# FPGA-DemoShield-Schematic.net
KiCad netlist of a schematic drawn in Altium Designer
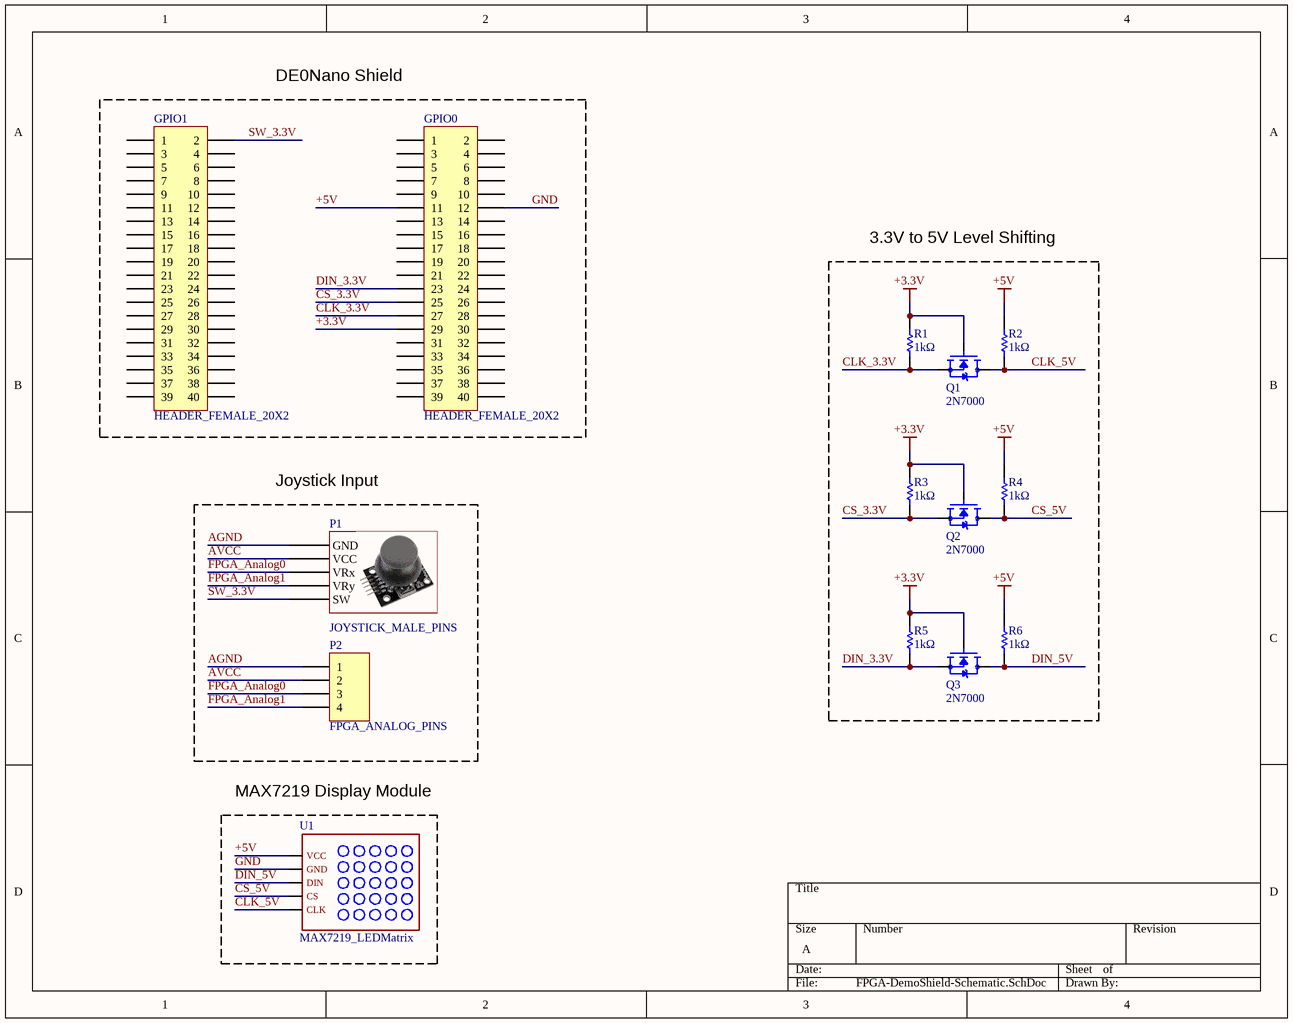
[diagram p0: FPGA-DemoShield-Schematic.SchDoc]

(export (version "E")
  (design (tool "Eeschema 10.0.6"))
  (components
    (comp (ref "GPIO0")
      (value "HEADER_FEMALE_20X2")
      (footprint "HDR2X20_FEMALE")
      (description "Header, 20-Pin, Dual row")
      (libsource (lib "FPGA-DemoShield-SchLib") (part "HEADER_FEMALE_20X2"))
    )
    (comp (ref "GPIO1")
      (value "HEADER_FEMALE_20X2")
      (footprint "HDR2X20_FEMALE")
      (description "Header, 20-Pin, Dual row")
      (libsource (lib "FPGA-DemoShield-SchLib") (part "HEADER_FEMALE_20X2"))
    )
    (comp (ref "P1")
      (value "JOYSTICK_MALE_PINS")
      (footprint "HDR1X5_MALE")
      (description "Header, 5-Pin")
      (libsource (lib "FPGA-DemoShield-SchLib") (part "JOYSTICK_MALE_PINS"))
    )
    (comp (ref "P2")
      (value "FPGA_ANALOG_PINS")
      (footprint "HDR1X4_MALE")
      (description "Header, 4-Pin")
      (libsource (lib "FPGA-DemoShield-SchLib") (part "FPGA_ANALOG_PINS"))
    )
    (comp (ref "Q1")
      (value "2N7000")
      (footprint "2N7000-TO-92")
      (description "MOSFET N-CH 60V 350MA TO92-3")
      (libsource (lib "FPGA-DemoShield-SchLib") (part "2N7000"))
    )
    (comp (ref "Q2")
      (value "2N7000")
      (footprint "2N7000-TO-92")
      (description "MOSFET N-CH 60V 350MA TO92-3")
      (libsource (lib "FPGA-DemoShield-SchLib") (part "2N7000"))
    )
    (comp (ref "Q3")
      (value "2N7000")
      (footprint "2N7000-TO-92")
      (description "MOSFET N-CH 60V 350MA TO92-3")
      (libsource (lib "FPGA-DemoShield-SchLib") (part "2N7000"))
    )
    (comp (ref "R1")
      (value "1kΩ")
      (footprint "RES_0805")
      (description "1k RES 0805")
      (fields (field (name "Comment") "RES_1k_0805") (field (name "PUBLISHER") "Altium Limited"))
      (libsource (lib "FPGA-DemoShield-SchLib") (part "RES_1k_0805"))
    )
    (comp (ref "R2")
      (value "1kΩ")
      (footprint "RES_0805")
      (description "1k RES 0805")
      (fields (field (name "Comment") "RES_1k_0805") (field (name "PUBLISHER") "Altium Limited"))
      (libsource (lib "FPGA-DemoShield-SchLib") (part "RES_1k_0805"))
    )
    (comp (ref "R3")
      (value "1kΩ")
      (footprint "RES_0805")
      (description "1k RES 0805")
      (fields (field (name "Comment") "RES_1k_0805") (field (name "PUBLISHER") "Altium Limited"))
      (libsource (lib "FPGA-DemoShield-SchLib") (part "RES_1k_0805"))
    )
    (comp (ref "R4")
      (value "1kΩ")
      (footprint "RES_0805")
      (description "1k RES 0805")
      (fields (field (name "Comment") "RES_1k_0805") (field (name "PUBLISHER") "Altium Limited"))
      (libsource (lib "FPGA-DemoShield-SchLib") (part "RES_1k_0805"))
    )
    (comp (ref "R5")
      (value "1kΩ")
      (footprint "RES_0805")
      (description "1k RES 0805")
      (fields (field (name "Comment") "RES_1k_0805") (field (name "PUBLISHER") "Altium Limited"))
      (libsource (lib "FPGA-DemoShield-SchLib") (part "RES_1k_0805"))
    )
    (comp (ref "R6")
      (value "1kΩ")
      (footprint "RES_0805")
      (description "1k RES 0805")
      (fields (field (name "Comment") "RES_1k_0805") (field (name "PUBLISHER") "Altium Limited"))
      (libsource (lib "FPGA-DemoShield-SchLib") (part "RES_1k_0805"))
    )
    (comp (ref "U1")
      (value "MAX7219_LEDMatrix")
      (footprint "LED_MATRIX")
      (description "LED MATRIX")
      (libsource (lib "FPGA-DemoShield-SchLib") (part "MAX7219_LEDMatrix"))
    )
  )
  (nets
    (net (code "1") (name "+3.3V") (class "Default")
      (node (ref "GPIO0") (pin "29") (pinfunction "29_29") (pintype "passive"))
      (node (ref "Q1") (pin "2") (pinfunction "G_2") (pintype "passive"))
      (node (ref "Q2") (pin "2") (pinfunction "G_2") (pintype "passive"))
      (node (ref "Q3") (pin "2") (pinfunction "G_2") (pintype "passive"))
      (node (ref "R1") (pin "2") (pinfunction "2_2") (pintype "passive"))
      (node (ref "R3") (pin "2") (pinfunction "2_2") (pintype "passive"))
      (node (ref "R5") (pin "2") (pinfunction "2_2") (pintype "passive"))
    )
    (net (code "2") (name "+5V") (class "Default")
      (node (ref "GPIO0") (pin "11") (pinfunction "11_11") (pintype "passive"))
      (node (ref "R2") (pin "2") (pinfunction "2_2") (pintype "passive"))
      (node (ref "R4") (pin "2") (pinfunction "2_2") (pintype "passive"))
      (node (ref "R6") (pin "2") (pinfunction "2_2") (pintype "passive"))
      (node (ref "U1") (pin "1") (pinfunction "VCC_1") (pintype "passive"))
    )
    (net (code "3") (name "/AGND") (class "Default")
      (node (ref "P1") (pin "1") (pinfunction "GND_1") (pintype "passive"))
      (node (ref "P2") (pin "1") (pinfunction "1_1") (pintype "passive"))
    )
    (net (code "4") (name "/AVCC") (class "Default")
      (node (ref "P1") (pin "2") (pinfunction "VCC_2") (pintype "passive"))
      (node (ref "P2") (pin "2") (pinfunction "2_2") (pintype "passive"))
    )
    (net (code "5") (name "/CLK_3.3V") (class "Default")
      (node (ref "GPIO0") (pin "27") (pinfunction "27_27") (pintype "passive"))
      (node (ref "Q1") (pin "1") (pinfunction "S_1") (pintype "passive"))
      (node (ref "R1") (pin "1") (pinfunction "1_1") (pintype "passive"))
    )
    (net (code "6") (name "/CLK_5V") (class "Default")
      (node (ref "Q1") (pin "3") (pinfunction "D_3") (pintype "passive"))
      (node (ref "R2") (pin "1") (pinfunction "1_1") (pintype "passive"))
      (node (ref "U1") (pin "5") (pinfunction "CLK_5") (pintype "passive"))
    )
    (net (code "7") (name "/CS_3.3V") (class "Default")
      (node (ref "GPIO0") (pin "25") (pinfunction "25_25") (pintype "passive"))
      (node (ref "Q2") (pin "1") (pinfunction "S_1") (pintype "passive"))
      (node (ref "R3") (pin "1") (pinfunction "1_1") (pintype "passive"))
    )
    (net (code "8") (name "/CS_5V") (class "Default")
      (node (ref "Q2") (pin "3") (pinfunction "D_3") (pintype "passive"))
      (node (ref "R4") (pin "1") (pinfunction "1_1") (pintype "passive"))
      (node (ref "U1") (pin "4") (pinfunction "CS_4") (pintype "passive"))
    )
    (net (code "9") (name "/DIN_3.3V") (class "Default")
      (node (ref "GPIO0") (pin "23") (pinfunction "23_23") (pintype "passive"))
      (node (ref "Q3") (pin "1") (pinfunction "S_1") (pintype "passive"))
      (node (ref "R5") (pin "1") (pinfunction "1_1") (pintype "passive"))
    )
    (net (code "10") (name "/DIN_5V") (class "Default")
      (node (ref "Q3") (pin "3") (pinfunction "D_3") (pintype "passive"))
      (node (ref "R6") (pin "1") (pinfunction "1_1") (pintype "passive"))
      (node (ref "U1") (pin "3") (pinfunction "DIN_3") (pintype "passive"))
    )
    (net (code "11") (name "/FPGA_Analog0") (class "Default")
      (node (ref "P1") (pin "3") (pinfunction "VRx_3") (pintype "passive"))
      (node (ref "P2") (pin "3") (pinfunction "3_3") (pintype "passive"))
    )
    (net (code "12") (name "/FPGA_Analog1") (class "Default")
      (node (ref "P1") (pin "4") (pinfunction "VRy_4") (pintype "passive"))
      (node (ref "P2") (pin "4") (pinfunction "4_4") (pintype "passive"))
    )
    (net (code "13") (name "/GND") (class "Default")
      (node (ref "GPIO0") (pin "12") (pinfunction "12_12") (pintype "passive"))
      (node (ref "U1") (pin "2") (pinfunction "GND_2") (pintype "passive"))
    )
    (net (code "14") (name "/SW_3.3V") (class "Default")
      (node (ref "GPIO1") (pin "2") (pinfunction "2_2") (pintype "passive"))
      (node (ref "P1") (pin "5") (pinfunction "SW_5") (pintype "passive"))
    )
    (net (code "15") (name "unconnected-(GPIO0-Pad1)") (class "Default")
      (node (ref "GPIO0") (pin "1") (pinfunction "1_1") (pintype "passive"))
    )
    (net (code "16") (name "unconnected-(GPIO0-Pad2)") (class "Default")
      (node (ref "GPIO0") (pin "2") (pinfunction "2_2") (pintype "passive"))
    )
    (net (code "17") (name "unconnected-(GPIO0-Pad3)") (class "Default")
      (node (ref "GPIO0") (pin "3") (pinfunction "3_3") (pintype "passive"))
    )
    (net (code "18") (name "unconnected-(GPIO0-Pad4)") (class "Default")
      (node (ref "GPIO0") (pin "4") (pinfunction "4_4") (pintype "passive"))
    )
    (net (code "19") (name "unconnected-(GPIO0-Pad5)") (class "Default")
      (node (ref "GPIO0") (pin "5") (pinfunction "5_5") (pintype "passive"))
    )
    (net (code "20") (name "unconnected-(GPIO0-Pad6)") (class "Default")
      (node (ref "GPIO0") (pin "6") (pinfunction "6_6") (pintype "passive"))
    )
    (net (code "21") (name "unconnected-(GPIO0-Pad7)") (class "Default")
      (node (ref "GPIO0") (pin "7") (pinfunction "7_7") (pintype "passive"))
    )
    (net (code "22") (name "unconnected-(GPIO0-Pad8)") (class "Default")
      (node (ref "GPIO0") (pin "8") (pinfunction "8_8") (pintype "passive"))
    )
    (net (code "23") (name "unconnected-(GPIO0-Pad9)") (class "Default")
      (node (ref "GPIO0") (pin "9") (pinfunction "9_9") (pintype "passive"))
    )
    (net (code "24") (name "unconnected-(GPIO0-Pad10)") (class "Default")
      (node (ref "GPIO0") (pin "10") (pinfunction "10_10") (pintype "passive"))
    )
    (net (code "25") (name "unconnected-(GPIO0-Pad13)") (class "Default")
      (node (ref "GPIO0") (pin "13") (pinfunction "13_13") (pintype "passive"))
    )
    (net (code "26") (name "unconnected-(GPIO0-Pad14)") (class "Default")
      (node (ref "GPIO0") (pin "14") (pinfunction "14_14") (pintype "passive"))
    )
    (net (code "27") (name "unconnected-(GPIO0-Pad15)") (class "Default")
      (node (ref "GPIO0") (pin "15") (pinfunction "15_15") (pintype "passive"))
    )
    (net (code "28") (name "unconnected-(GPIO0-Pad16)") (class "Default")
      (node (ref "GPIO0") (pin "16") (pinfunction "16_16") (pintype "passive"))
    )
    (net (code "29") (name "unconnected-(GPIO0-Pad17)") (class "Default")
      (node (ref "GPIO0") (pin "17") (pinfunction "17_17") (pintype "passive"))
    )
    (net (code "30") (name "unconnected-(GPIO0-Pad18)") (class "Default")
      (node (ref "GPIO0") (pin "18") (pinfunction "18_18") (pintype "passive"))
    )
    (net (code "31") (name "unconnected-(GPIO0-Pad19)") (class "Default")
      (node (ref "GPIO0") (pin "19") (pinfunction "19_19") (pintype "passive"))
    )
    (net (code "32") (name "unconnected-(GPIO0-Pad20)") (class "Default")
      (node (ref "GPIO0") (pin "20") (pinfunction "20_20") (pintype "passive"))
    )
    (net (code "33") (name "unconnected-(GPIO0-Pad21)") (class "Default")
      (node (ref "GPIO0") (pin "21") (pinfunction "21_21") (pintype "passive"))
    )
    (net (code "34") (name "unconnected-(GPIO0-Pad22)") (class "Default")
      (node (ref "GPIO0") (pin "22") (pinfunction "22_22") (pintype "passive"))
    )
    (net (code "35") (name "unconnected-(GPIO0-Pad24)") (class "Default")
      (node (ref "GPIO0") (pin "24") (pinfunction "24_24") (pintype "passive"))
    )
    (net (code "36") (name "unconnected-(GPIO0-Pad26)") (class "Default")
      (node (ref "GPIO0") (pin "26") (pinfunction "26_26") (pintype "passive"))
    )
    (net (code "37") (name "unconnected-(GPIO0-Pad28)") (class "Default")
      (node (ref "GPIO0") (pin "28") (pinfunction "28_28") (pintype "passive"))
    )
    (net (code "38") (name "unconnected-(GPIO0-Pad30)") (class "Default")
      (node (ref "GPIO0") (pin "30") (pinfunction "30_30") (pintype "passive"))
    )
    (net (code "39") (name "unconnected-(GPIO0-Pad31)") (class "Default")
      (node (ref "GPIO0") (pin "31") (pinfunction "31_31") (pintype "passive"))
    )
    (net (code "40") (name "unconnected-(GPIO0-Pad32)") (class "Default")
      (node (ref "GPIO0") (pin "32") (pinfunction "32_32") (pintype "passive"))
    )
    (net (code "41") (name "unconnected-(GPIO0-Pad33)") (class "Default")
      (node (ref "GPIO0") (pin "33") (pinfunction "33_33") (pintype "passive"))
    )
    (net (code "42") (name "unconnected-(GPIO0-Pad34)") (class "Default")
      (node (ref "GPIO0") (pin "34") (pinfunction "34_34") (pintype "passive"))
    )
    (net (code "43") (name "unconnected-(GPIO0-Pad35)") (class "Default")
      (node (ref "GPIO0") (pin "35") (pinfunction "35_35") (pintype "passive"))
    )
    (net (code "44") (name "unconnected-(GPIO0-Pad36)") (class "Default")
      (node (ref "GPIO0") (pin "36") (pinfunction "36_36") (pintype "passive"))
    )
    (net (code "45") (name "unconnected-(GPIO0-Pad37)") (class "Default")
      (node (ref "GPIO0") (pin "37") (pinfunction "37_37") (pintype "passive"))
    )
    (net (code "46") (name "unconnected-(GPIO0-Pad38)") (class "Default")
      (node (ref "GPIO0") (pin "38") (pinfunction "38_38") (pintype "passive"))
    )
    (net (code "47") (name "unconnected-(GPIO0-Pad39)") (class "Default")
      (node (ref "GPIO0") (pin "39") (pinfunction "39_39") (pintype "passive"))
    )
    (net (code "48") (name "unconnected-(GPIO0-Pad40)") (class "Default")
      (node (ref "GPIO0") (pin "40") (pinfunction "40_40") (pintype "passive"))
    )
    (net (code "49") (name "unconnected-(GPIO1-Pad1)") (class "Default")
      (node (ref "GPIO1") (pin "1") (pinfunction "1_1") (pintype "passive"))
    )
    (net (code "50") (name "unconnected-(GPIO1-Pad3)") (class "Default")
      (node (ref "GPIO1") (pin "3") (pinfunction "3_3") (pintype "passive"))
    )
    (net (code "51") (name "unconnected-(GPIO1-Pad4)") (class "Default")
      (node (ref "GPIO1") (pin "4") (pinfunction "4_4") (pintype "passive"))
    )
    (net (code "52") (name "unconnected-(GPIO1-Pad5)") (class "Default")
      (node (ref "GPIO1") (pin "5") (pinfunction "5_5") (pintype "passive"))
    )
    (net (code "53") (name "unconnected-(GPIO1-Pad6)") (class "Default")
      (node (ref "GPIO1") (pin "6") (pinfunction "6_6") (pintype "passive"))
    )
    (net (code "54") (name "unconnected-(GPIO1-Pad7)") (class "Default")
      (node (ref "GPIO1") (pin "7") (pinfunction "7_7") (pintype "passive"))
    )
    (net (code "55") (name "unconnected-(GPIO1-Pad8)") (class "Default")
      (node (ref "GPIO1") (pin "8") (pinfunction "8_8") (pintype "passive"))
    )
    (net (code "56") (name "unconnected-(GPIO1-Pad9)") (class "Default")
      (node (ref "GPIO1") (pin "9") (pinfunction "9_9") (pintype "passive"))
    )
    (net (code "57") (name "unconnected-(GPIO1-Pad10)") (class "Default")
      (node (ref "GPIO1") (pin "10") (pinfunction "10_10") (pintype "passive"))
    )
    (net (code "58") (name "unconnected-(GPIO1-Pad11)") (class "Default")
      (node (ref "GPIO1") (pin "11") (pinfunction "11_11") (pintype "passive"))
    )
    (net (code "59") (name "unconnected-(GPIO1-Pad12)") (class "Default")
      (node (ref "GPIO1") (pin "12") (pinfunction "12_12") (pintype "passive"))
    )
    (net (code "60") (name "unconnected-(GPIO1-Pad13)") (class "Default")
      (node (ref "GPIO1") (pin "13") (pinfunction "13_13") (pintype "passive"))
    )
    (net (code "61") (name "unconnected-(GPIO1-Pad14)") (class "Default")
      (node (ref "GPIO1") (pin "14") (pinfunction "14_14") (pintype "passive"))
    )
    (net (code "62") (name "unconnected-(GPIO1-Pad15)") (class "Default")
      (node (ref "GPIO1") (pin "15") (pinfunction "15_15") (pintype "passive"))
    )
    (net (code "63") (name "unconnected-(GPIO1-Pad16)") (class "Default")
      (node (ref "GPIO1") (pin "16") (pinfunction "16_16") (pintype "passive"))
    )
    (net (code "64") (name "unconnected-(GPIO1-Pad17)") (class "Default")
      (node (ref "GPIO1") (pin "17") (pinfunction "17_17") (pintype "passive"))
    )
    (net (code "65") (name "unconnected-(GPIO1-Pad18)") (class "Default")
      (node (ref "GPIO1") (pin "18") (pinfunction "18_18") (pintype "passive"))
    )
    (net (code "66") (name "unconnected-(GPIO1-Pad19)") (class "Default")
      (node (ref "GPIO1") (pin "19") (pinfunction "19_19") (pintype "passive"))
    )
    (net (code "67") (name "unconnected-(GPIO1-Pad20)") (class "Default")
      (node (ref "GPIO1") (pin "20") (pinfunction "20_20") (pintype "passive"))
    )
    (net (code "68") (name "unconnected-(GPIO1-Pad21)") (class "Default")
      (node (ref "GPIO1") (pin "21") (pinfunction "21_21") (pintype "passive"))
    )
    (net (code "69") (name "unconnected-(GPIO1-Pad22)") (class "Default")
      (node (ref "GPIO1") (pin "22") (pinfunction "22_22") (pintype "passive"))
    )
    (net (code "70") (name "unconnected-(GPIO1-Pad23)") (class "Default")
      (node (ref "GPIO1") (pin "23") (pinfunction "23_23") (pintype "passive"))
    )
    (net (code "71") (name "unconnected-(GPIO1-Pad24)") (class "Default")
      (node (ref "GPIO1") (pin "24") (pinfunction "24_24") (pintype "passive"))
    )
    (net (code "72") (name "unconnected-(GPIO1-Pad25)") (class "Default")
      (node (ref "GPIO1") (pin "25") (pinfunction "25_25") (pintype "passive"))
    )
    (net (code "73") (name "unconnected-(GPIO1-Pad26)") (class "Default")
      (node (ref "GPIO1") (pin "26") (pinfunction "26_26") (pintype "passive"))
    )
    (net (code "74") (name "unconnected-(GPIO1-Pad27)") (class "Default")
      (node (ref "GPIO1") (pin "27") (pinfunction "27_27") (pintype "passive"))
    )
    (net (code "75") (name "unconnected-(GPIO1-Pad28)") (class "Default")
      (node (ref "GPIO1") (pin "28") (pinfunction "28_28") (pintype "passive"))
    )
    (net (code "76") (name "unconnected-(GPIO1-Pad29)") (class "Default")
      (node (ref "GPIO1") (pin "29") (pinfunction "29_29") (pintype "passive"))
    )
    (net (code "77") (name "unconnected-(GPIO1-Pad30)") (class "Default")
      (node (ref "GPIO1") (pin "30") (pinfunction "30_30") (pintype "passive"))
    )
    (net (code "78") (name "unconnected-(GPIO1-Pad31)") (class "Default")
      (node (ref "GPIO1") (pin "31") (pinfunction "31_31") (pintype "passive"))
    )
    (net (code "79") (name "unconnected-(GPIO1-Pad32)") (class "Default")
      (node (ref "GPIO1") (pin "32") (pinfunction "32_32") (pintype "passive"))
    )
    (net (code "80") (name "unconnected-(GPIO1-Pad33)") (class "Default")
      (node (ref "GPIO1") (pin "33") (pinfunction "33_33") (pintype "passive"))
    )
    (net (code "81") (name "unconnected-(GPIO1-Pad34)") (class "Default")
      (node (ref "GPIO1") (pin "34") (pinfunction "34_34") (pintype "passive"))
    )
    (net (code "82") (name "unconnected-(GPIO1-Pad35)") (class "Default")
      (node (ref "GPIO1") (pin "35") (pinfunction "35_35") (pintype "passive"))
    )
    (net (code "83") (name "unconnected-(GPIO1-Pad36)") (class "Default")
      (node (ref "GPIO1") (pin "36") (pinfunction "36_36") (pintype "passive"))
    )
    (net (code "84") (name "unconnected-(GPIO1-Pad37)") (class "Default")
      (node (ref "GPIO1") (pin "37") (pinfunction "37_37") (pintype "passive"))
    )
    (net (code "85") (name "unconnected-(GPIO1-Pad38)") (class "Default")
      (node (ref "GPIO1") (pin "38") (pinfunction "38_38") (pintype "passive"))
    )
    (net (code "86") (name "unconnected-(GPIO1-Pad39)") (class "Default")
      (node (ref "GPIO1") (pin "39") (pinfunction "39_39") (pintype "passive"))
    )
    (net (code "87") (name "unconnected-(GPIO1-Pad40)") (class "Default")
      (node (ref "GPIO1") (pin "40") (pinfunction "40_40") (pintype "passive"))
    )
  )
)
